# estop-lora-esp32.net
KiCad netlist of a schematic drawn in Altium Designer
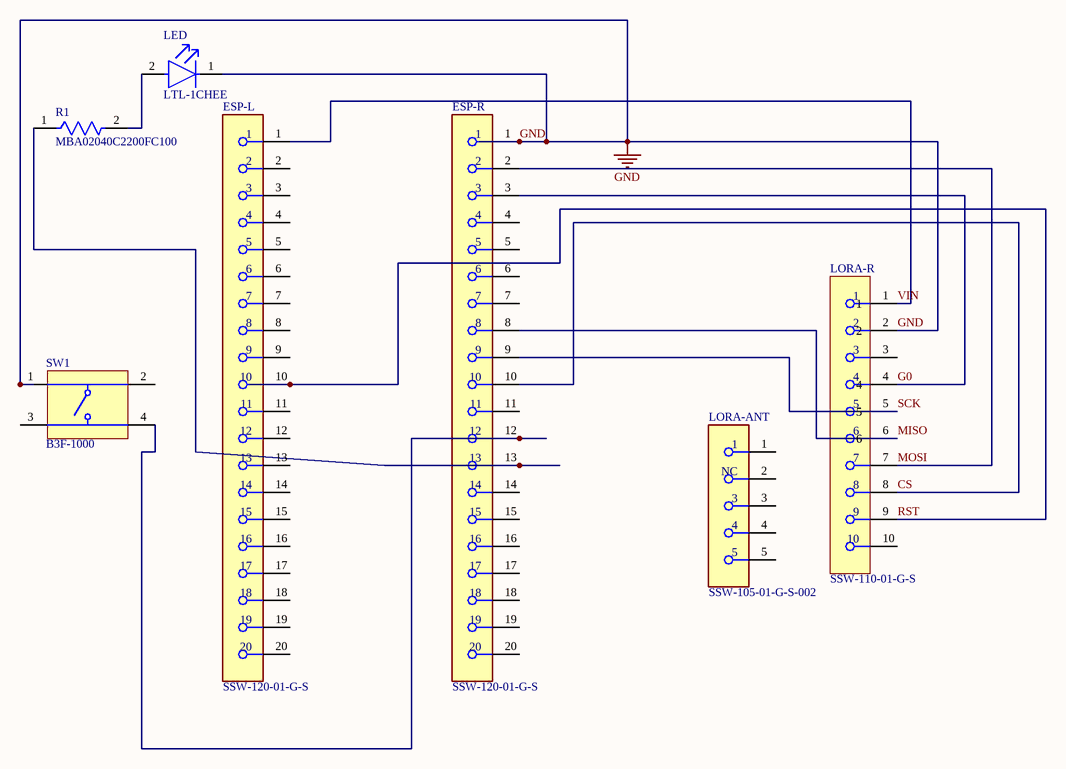
[diagram p0: estop-lora-esp32.SchDoc]

(export (version "E")
  (design (tool "Eeschema 10.0.6"))
  (components
    (comp (ref "ESP-L")
      (value "SSW-120-01-G-S")
      (footprint "FP-SSW-120-01-G-S-MFG")
      (description "SSW-120-01-G-S SSW - Samtec 2.54mm Single Row Straight Socket Strip 8.5 Profile (mcv)(TO22)")
      (libsource (lib "Altium Content Vault") (part "dba14e038e6f7492952b7f1e871f183"))
    )
    (comp (ref "ESP-R")
      (value "SSW-120-01-G-S")
      (footprint "FP-SSW-120-01-G-S-MFG")
      (description "SSW-120-01-G-S SSW - Samtec 2.54mm Single Row Straight Socket Strip 8.5 Profile (mcv)(TO22)")
      (libsource (lib "Altium Content Vault") (part "dba14e038e6f7492952b7f1e871f183"))
    )
    (comp (ref "LED")
      (value "LTL-1CHEE")
      (footprint "FP-LTL-1CHEE-MFG")
      (description "LED RED CLEAR T/H")
      (libsource (lib "Altium Content Vault") (part "8706943c75ba83719d021d2fdc84c58"))
    )
    (comp (ref "LORA-ANT")
      (value "SSW-105-01-G-S-002")
      (footprint "FP-SSW-105-01-G-S-002-MFG")
      (description "CONN RCPT 5POS 0.1 GOLD PCB")
      (fields
        (field (name "OCTOPART") "https://octopart.com/ssw-105-01-g-s-002-samtec-17275695")
        (field (name "MANUFACTURER") "Samtec")
      )
      (libsource (lib "Altium Content Vault") (part "983be75d0d48fdddaa0c0ee7a70df29"))
    )
    (comp (ref "LORA-R")
      (value "SSW-110-01-G-S")
      (footprint "FP-SSW-110-01-G-S-MFG")
      (libsource (lib "Altium Content Vault") (part "a6b0ccc4a6f32c6729440d11cede569"))
    )
    (comp (ref "R1")
      (value "MBA02040C2200FC100")
      (footprint "FP-MBA0204-MFG")
      (description "RES 220 OHM 0.4W 1% AXIAL")
      (fields
        (field (name "OCTOPART") "https://octopart.com/mba02040c2200fc100-vishay-43743094")
        (field (name "MANUFACTURER") "Vishay BC Components")
      )
      (libsource (lib "Altium Content Vault") (part "1029c3af85768c4190bb7ad29bc67b5"))
    )
    (comp (ref "SW1")
      (value "B3F-1000")
      (footprint "OMRON-B3F-1000-4_V")
      (description "Tactile Switch, SPST-NO, 0.05 A, 5 to 24 V, -25 to 70 degC, 4-Pin THD, RoHS, Bulk")
      (libsource (lib "Altium Content Vault") (part "SW-SPST-4_A"))
    )
  )
  (nets
    (net (code "1") (name "/CS") (class "Default")
      (node (ref "ESP-R") (pin "10") (pinfunction "10_10") (pintype "passive"))
      (node (ref "LORA-R") (pin "8") (pinfunction "8_8") (pintype "passive"))
    )
    (net (code "2") (name "/G0") (class "Default")
      (node (ref "ESP-R") (pin "3") (pinfunction "3_3") (pintype "passive"))
      (node (ref "LORA-R") (pin "4") (pinfunction "4_4") (pintype "passive"))
    )
    (net (code "3") (name "/MISO") (class "Default")
      (node (ref "ESP-R") (pin "8") (pinfunction "8_8") (pintype "passive"))
      (node (ref "LORA-R") (pin "6") (pinfunction "6_6") (pintype "passive"))
    )
    (net (code "4") (name "/MOSI") (class "Default")
      (node (ref "ESP-R") (pin "2") (pinfunction "2_2") (pintype "passive"))
      (node (ref "LORA-R") (pin "7") (pinfunction "7_7") (pintype "passive"))
    )
    (net (code "5") (name "/RST") (class "Default")
      (node (ref "ESP-L") (pin "10") (pinfunction "10_10") (pintype "passive"))
      (node (ref "LORA-R") (pin "9") (pinfunction "9_9") (pintype "passive"))
    )
    (net (code "6") (name "/SCK") (class "Default")
      (node (ref "ESP-R") (pin "9") (pinfunction "9_9") (pintype "passive"))
      (node (ref "LORA-R") (pin "5") (pinfunction "5_5") (pintype "passive"))
    )
    (net (code "7") (name "/VIN") (class "Default")
      (node (ref "ESP-L") (pin "1") (pinfunction "1_1") (pintype "passive"))
      (node (ref "LORA-R") (pin "1") (pinfunction "1_1") (pintype "passive"))
    )
    (net (code "8") (name "GND") (class "Default")
      (node (ref "ESP-R") (pin "1") (pinfunction "1_1") (pintype "passive"))
      (node (ref "LED") (pin "1") (pinfunction "C_1") (pintype "passive"))
      (node (ref "LORA-R") (pin "2") (pinfunction "2_2") (pintype "passive"))
      (node (ref "SW1") (pin "1") (pinfunction "1_1") (pintype "passive"))
    )
    (net (code "9") (name "Net-(ESP-R-Pad12)") (class "Default")
      (node (ref "ESP-R") (pin "12") (pinfunction "12_12") (pintype "passive"))
      (node (ref "SW1") (pin "4") (pinfunction "4_4") (pintype "passive"))
    )
    (net (code "10") (name "Net-(ESP-R-Pad13)") (class "Default")
      (node (ref "ESP-R") (pin "13") (pinfunction "13_13") (pintype "passive"))
      (node (ref "R1") (pin "1") (pinfunction "1_1") (pintype "passive"))
    )
    (net (code "11") (name "Net-(LED-A)") (class "Default")
      (node (ref "LED") (pin "2") (pinfunction "A_2") (pintype "passive"))
      (node (ref "R1") (pin "2") (pinfunction "2_2") (pintype "passive"))
    )
    (net (code "12") (name "unconnected-(ESP-L-Pad2)") (class "Default")
      (node (ref "ESP-L") (pin "2") (pinfunction "2_2") (pintype "passive"))
    )
    (net (code "13") (name "unconnected-(ESP-L-Pad3)") (class "Default")
      (node (ref "ESP-L") (pin "3") (pinfunction "3_3") (pintype "passive"))
    )
    (net (code "14") (name "unconnected-(ESP-L-Pad4)") (class "Default")
      (node (ref "ESP-L") (pin "4") (pinfunction "4_4") (pintype "passive"))
    )
    (net (code "15") (name "unconnected-(ESP-L-Pad5)") (class "Default")
      (node (ref "ESP-L") (pin "5") (pinfunction "5_5") (pintype "passive"))
    )
    (net (code "16") (name "unconnected-(ESP-L-Pad6)") (class "Default")
      (node (ref "ESP-L") (pin "6") (pinfunction "6_6") (pintype "passive"))
    )
    (net (code "17") (name "unconnected-(ESP-L-Pad7)") (class "Default")
      (node (ref "ESP-L") (pin "7") (pinfunction "7_7") (pintype "passive"))
    )
    (net (code "18") (name "unconnected-(ESP-L-Pad8)") (class "Default")
      (node (ref "ESP-L") (pin "8") (pinfunction "8_8") (pintype "passive"))
    )
    (net (code "19") (name "unconnected-(ESP-L-Pad9)") (class "Default")
      (node (ref "ESP-L") (pin "9") (pinfunction "9_9") (pintype "passive"))
    )
    (net (code "20") (name "unconnected-(ESP-L-Pad11)") (class "Default")
      (node (ref "ESP-L") (pin "11") (pinfunction "11_11") (pintype "passive"))
    )
    (net (code "21") (name "unconnected-(ESP-L-Pad12)") (class "Default")
      (node (ref "ESP-L") (pin "12") (pinfunction "12_12") (pintype "passive"))
    )
    (net (code "22") (name "unconnected-(ESP-L-Pad13)") (class "Default")
      (node (ref "ESP-L") (pin "13") (pinfunction "13_13") (pintype "passive"))
    )
    (net (code "23") (name "unconnected-(ESP-L-Pad14)") (class "Default")
      (node (ref "ESP-L") (pin "14") (pinfunction "14_14") (pintype "passive"))
    )
    (net (code "24") (name "unconnected-(ESP-L-Pad15)") (class "Default")
      (node (ref "ESP-L") (pin "15") (pinfunction "15_15") (pintype "passive"))
    )
    (net (code "25") (name "unconnected-(ESP-L-Pad16)") (class "Default")
      (node (ref "ESP-L") (pin "16") (pinfunction "16_16") (pintype "passive"))
    )
    (net (code "26") (name "unconnected-(ESP-L-Pad17)") (class "Default")
      (node (ref "ESP-L") (pin "17") (pinfunction "17_17") (pintype "passive"))
    )
    (net (code "27") (name "unconnected-(ESP-L-Pad18)") (class "Default")
      (node (ref "ESP-L") (pin "18") (pinfunction "18_18") (pintype "passive"))
    )
    (net (code "28") (name "unconnected-(ESP-L-Pad19)") (class "Default")
      (node (ref "ESP-L") (pin "19") (pinfunction "19_19") (pintype "passive"))
    )
    (net (code "29") (name "unconnected-(ESP-L-Pad20)") (class "Default")
      (node (ref "ESP-L") (pin "20") (pinfunction "20_20") (pintype "passive"))
    )
    (net (code "30") (name "unconnected-(ESP-R-Pad4)") (class "Default")
      (node (ref "ESP-R") (pin "4") (pinfunction "4_4") (pintype "passive"))
    )
    (net (code "31") (name "unconnected-(ESP-R-Pad5)") (class "Default")
      (node (ref "ESP-R") (pin "5") (pinfunction "5_5") (pintype "passive"))
    )
    (net (code "32") (name "unconnected-(ESP-R-Pad6)") (class "Default")
      (node (ref "ESP-R") (pin "6") (pinfunction "6_6") (pintype "passive"))
    )
    (net (code "33") (name "unconnected-(ESP-R-Pad7)") (class "Default")
      (node (ref "ESP-R") (pin "7") (pinfunction "7_7") (pintype "passive"))
    )
    (net (code "34") (name "unconnected-(ESP-R-Pad11)") (class "Default")
      (node (ref "ESP-R") (pin "11") (pinfunction "11_11") (pintype "passive"))
    )
    (net (code "35") (name "unconnected-(ESP-R-Pad14)") (class "Default")
      (node (ref "ESP-R") (pin "14") (pinfunction "14_14") (pintype "passive"))
    )
    (net (code "36") (name "unconnected-(ESP-R-Pad15)") (class "Default")
      (node (ref "ESP-R") (pin "15") (pinfunction "15_15") (pintype "passive"))
    )
    (net (code "37") (name "unconnected-(ESP-R-Pad16)") (class "Default")
      (node (ref "ESP-R") (pin "16") (pinfunction "16_16") (pintype "passive"))
    )
    (net (code "38") (name "unconnected-(ESP-R-Pad17)") (class "Default")
      (node (ref "ESP-R") (pin "17") (pinfunction "17_17") (pintype "passive"))
    )
    (net (code "39") (name "unconnected-(ESP-R-Pad18)") (class "Default")
      (node (ref "ESP-R") (pin "18") (pinfunction "18_18") (pintype "passive"))
    )
    (net (code "40") (name "unconnected-(ESP-R-Pad19)") (class "Default")
      (node (ref "ESP-R") (pin "19") (pinfunction "19_19") (pintype "passive"))
    )
    (net (code "41") (name "unconnected-(ESP-R-Pad20)") (class "Default")
      (node (ref "ESP-R") (pin "20") (pinfunction "20_20") (pintype "passive"))
    )
    (net (code "42") (name "unconnected-(LORA-ANT-NC-Pad2)") (class "Default")
      (node (ref "LORA-ANT") (pin "2") (pinfunction "NC_2") (pintype "passive"))
    )
    (net (code "43") (name "unconnected-(LORA-ANT-Pad1)") (class "Default")
      (node (ref "LORA-ANT") (pin "1") (pinfunction "1_1") (pintype "passive"))
    )
    (net (code "44") (name "unconnected-(LORA-ANT-Pad3)") (class "Default")
      (node (ref "LORA-ANT") (pin "3") (pinfunction "3_3") (pintype "passive"))
    )
    (net (code "45") (name "unconnected-(LORA-ANT-Pad4)") (class "Default")
      (node (ref "LORA-ANT") (pin "4") (pinfunction "4_4") (pintype "passive"))
    )
    (net (code "46") (name "unconnected-(LORA-ANT-Pad5)") (class "Default")
      (node (ref "LORA-ANT") (pin "5") (pinfunction "5_5") (pintype "passive"))
    )
    (net (code "47") (name "unconnected-(LORA-R-Pad3)") (class "Default")
      (node (ref "LORA-R") (pin "3") (pinfunction "3_3") (pintype "passive"))
    )
    (net (code "48") (name "unconnected-(LORA-R-Pad10)") (class "Default")
      (node (ref "LORA-R") (pin "10") (pinfunction "10_10") (pintype "passive"))
    )
    (net (code "49") (name "unconnected-(SW1-Pad2)") (class "Default")
      (node (ref "SW1") (pin "2") (pinfunction "2_2") (pintype "passive"))
    )
    (net (code "50") (name "unconnected-(SW1-Pad3)") (class "Default")
      (node (ref "SW1") (pin "3") (pinfunction "3_3") (pintype "passive"))
    )
  )
)
